# current_only.net
KiCad netlist of a schematic drawn in EAGLE
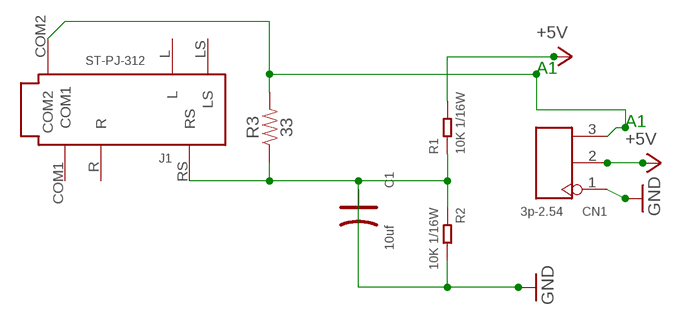
[diagram p0: schematic, sheet 1]

(export (version "E")
  (design (tool "Eeschema 10.0.6"))
  (components
    (comp (ref "C1")
      (value "10uf")
      (footprint "eagle-import:AVX-A")
      (fields (field (name "MPN") "TAJA106K010RNJ"))
      (libsource (lib "eagle-import") (part "TANTALUM-SMD-10UF-10V-10%(AVX-A)"))
    )
    (comp (ref "CN1")
      (value "3p-2.54")
      (footprint "eagle-import:H3-2.54")
      (libsource (lib "eagle-import") (part "DIP-BLACK-MALE-HEADER-VERT(3P-2.54)"))
    )
    (comp (ref "J1")
      (value "ST-PJ-312")
      (footprint "eagle-import:AUDIO6P-SMD-3.5-14.0X6.4X5.0MM")
      (libsource (lib "eagle-import") (part "AUDIO-JACK-6P-SMD(ST-PJ-312)"))
    )
    (comp (ref "R1")
      (value "10K 1/16W")
      (footprint "eagle-import:R0402")
      (fields (field (name "MPN") "RC0402FR-0710KL"))
      (libsource (lib "eagle-import") (part "SMD-RES-10K-1%-1/16W(0402)"))
    )
    (comp (ref "R2")
      (value "10K 1/16W")
      (footprint "eagle-import:R0402")
      (fields (field (name "MPN") "RC0402FR-0710KL"))
      (libsource (lib "eagle-import") (part "SMD-RES-10K-1%-1/16W(0402)"))
    )
    (comp (ref "R3")
      (value "33")
      (footprint "eagle-import:0603")
      (libsource (lib "eagle-import") (part "33OHM-0603-1/10W-1%"))
    )
  )
  (nets
    (net (code "1") (name "+5V") (class "Default")
      (node (ref "CN1") (pin "2") (pinfunction "P$2_2") (pintype "bidirectional"))
      (node (ref "R1") (pin "2") (pinfunction "2_2") (pintype "passive"))
    )
    (net (code "2") (name "GND") (class "Default")
      (node (ref "C1") (pin "+") (pinfunction "+_+") (pintype "passive"))
      (node (ref "CN1") (pin "1") (pinfunction "P$1_1") (pintype "bidirectional"))
      (node (ref "R2") (pin "2") (pinfunction "2_2") (pintype "passive"))
    )
    (net (code "3") (name "Net-(C1-Pad-)") (class "Default")
      (node (ref "C1") (pin "-") (pinfunction "-_-") (pintype "passive"))
      (node (ref "J1") (pin "RS") (pinfunction "RS_RS") (pintype "bidirectional"))
      (node (ref "R1") (pin "1") (pinfunction "1_1") (pintype "passive"))
      (node (ref "R2") (pin "1") (pinfunction "1_1") (pintype "passive"))
      (node (ref "R3") (pin "1") (pinfunction "1_1") (pintype "passive"))
    )
    (net (code "4") (name "Net-(CN1-P$3)") (class "Default")
      (node (ref "CN1") (pin "3") (pinfunction "P$3_3") (pintype "bidirectional"))
      (node (ref "J1") (pin "COM2") (pinfunction "COM2_COM2") (pintype "bidirectional"))
      (node (ref "R3") (pin "2") (pinfunction "2_2") (pintype "passive"))
    )
    (net (code "5") (name "unconnected-(J1-PadCOM1)") (class "Default")
      (node (ref "J1") (pin "COM1") (pinfunction "COM1_COM1") (pintype "bidirectional"))
    )
    (net (code "6") (name "unconnected-(J1-PadL)") (class "Default")
      (node (ref "J1") (pin "L") (pinfunction "L_L") (pintype "bidirectional"))
    )
    (net (code "7") (name "unconnected-(J1-PadLS)") (class "Default")
      (node (ref "J1") (pin "LS") (pinfunction "LS_LS") (pintype "bidirectional"))
    )
    (net (code "8") (name "unconnected-(J1-PadR)") (class "Default")
      (node (ref "J1") (pin "R") (pinfunction "R_R") (pintype "bidirectional"))
    )
  )
)
